# emitter.net
KiCad netlist of a schematic drawn in EAGLE
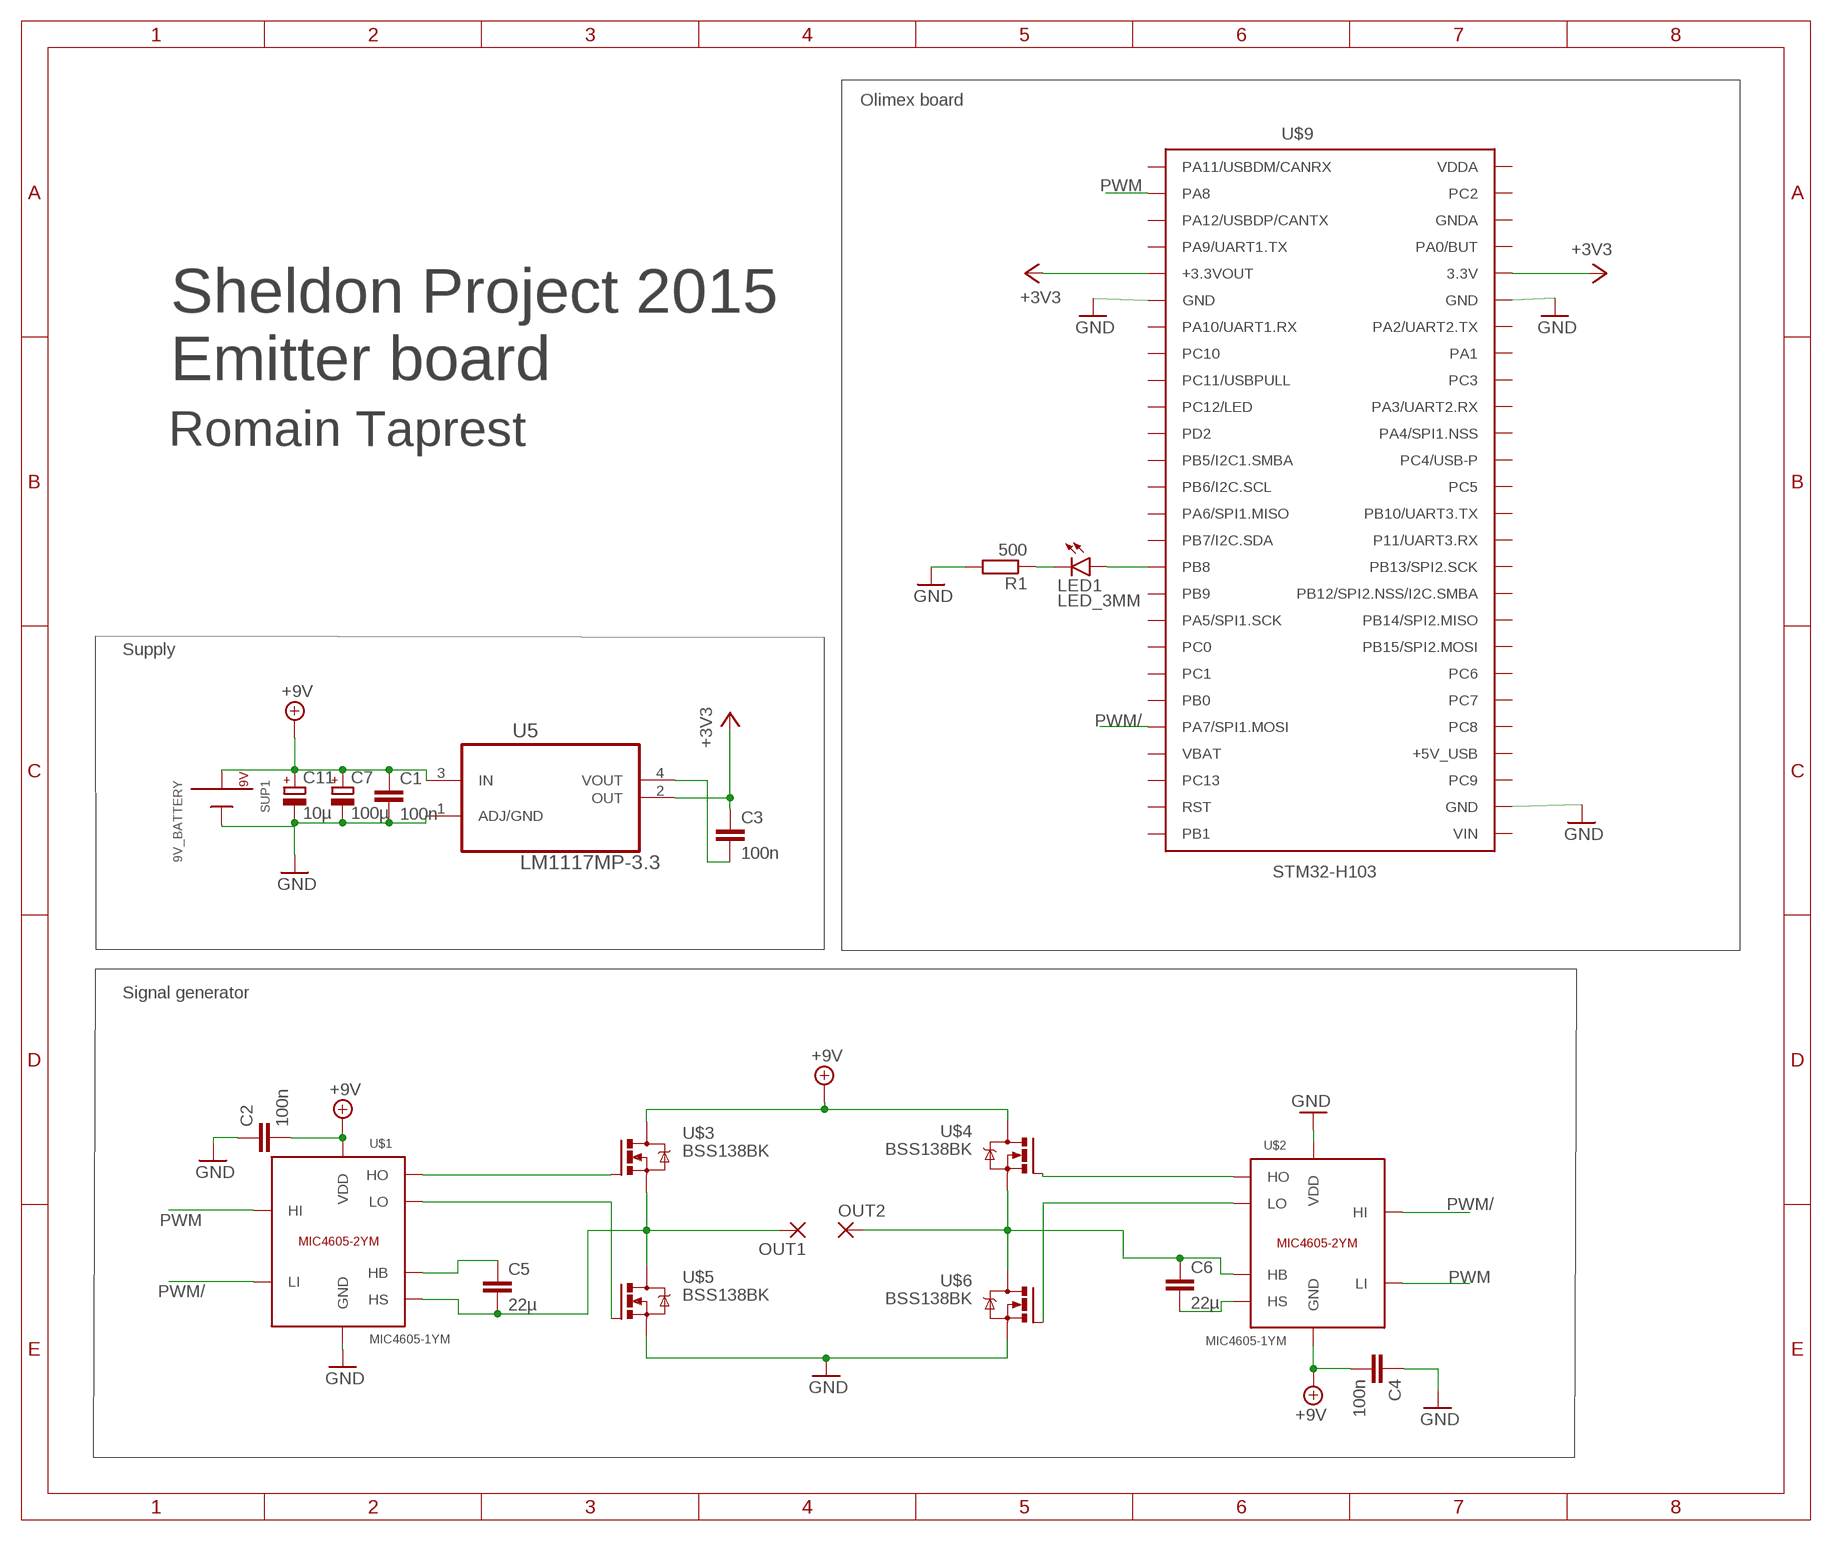
[diagram p0: schematic, sheet 1]

(export (version "E")
  (design (tool "Eeschema 10.0.6"))
  (components
    (comp (ref "C1")
      (value "100n")
      (footprint "eagle-import:C050-025X075")
      (libsource (lib "eagle-import") (part "C-EU050-025X075"))
    )
    (comp (ref "C2")
      (value "100n")
      (footprint "eagle-import:C050-025X075")
      (libsource (lib "eagle-import") (part "C-EU050-025X075"))
    )
    (comp (ref "C3")
      (value "100n")
      (footprint "eagle-import:C050-025X075")
      (libsource (lib "eagle-import") (part "C-EU050-025X075"))
    )
    (comp (ref "C4")
      (value "100n")
      (footprint "eagle-import:C050-025X075")
      (libsource (lib "eagle-import") (part "C-EU050-025X075"))
    )
    (comp (ref "C5")
      (value "22µ")
      (footprint "eagle-import:C050-025X075")
      (libsource (lib "eagle-import") (part "C-EU050-025X075"))
    )
    (comp (ref "C6")
      (value "22µ")
      (footprint "eagle-import:C050-025X075")
      (libsource (lib "eagle-import") (part "C-EU050-025X075"))
    )
    (comp (ref "C7")
      (value "100µ")
      (footprint "eagle-import:E2,5-6")
      (libsource (lib "eagle-import") (part "CPOL_DIAM5MM"))
    )
    (comp (ref "C11")
      (value "10µ")
      (footprint "eagle-import:E2,5-6")
      (libsource (lib "eagle-import") (part "CPOL_DIAM5MM"))
    )
    (comp (ref "LED1")
      (value "LED_3MM")
      (footprint "eagle-import:LED3MM")
      (libsource (lib "eagle-import") (part "LED_3MM"))
    )
    (comp (ref "OUT1")
      (value "2,54/1,0")
      (footprint "eagle-import:2,54_1,0")
      (libsource (lib "eagle-import") (part "2,54/1,0"))
    )
    (comp (ref "OUT2")
      (value "2,54/1,0")
      (footprint "eagle-import:2,54_1,0")
      (libsource (lib "eagle-import") (part "2,54/1,0"))
    )
    (comp (ref "R1")
      (value "500")
      (footprint "eagle-import:0207_10")
      (libsource (lib "eagle-import") (part "R-EU_0207/10"))
    )
    (comp (ref "SUP1")
      (value "9V_BATTERY")
      (footprint "eagle-import:9V_BATTERY")
      (libsource (lib "eagle-import") (part "9V_BATTERY"))
    )
    (comp (ref "U$1")
      (value "MIC4605-1YM")
      (footprint "eagle-import:SOIC08")
      (libsource (lib "eagle-import") (part "MIC4605-1YM"))
    )
    (comp (ref "U$2")
      (value "MIC4605-1YM")
      (footprint "eagle-import:SOIC08")
      (libsource (lib "eagle-import") (part "MIC4605-1YM"))
    )
    (comp (ref "U$3")
      (value "BSS138BK")
      (footprint "eagle-import:SOT23")
      (libsource (lib "eagle-import") (part "BSS138BK"))
    )
    (comp (ref "U$4")
      (value "BSS138BK")
      (footprint "eagle-import:SOT23")
      (libsource (lib "eagle-import") (part "BSS138BK"))
    )
    (comp (ref "U$5")
      (value "BSS138BK")
      (footprint "eagle-import:SOT23")
      (libsource (lib "eagle-import") (part "BSS138BK"))
    )
    (comp (ref "U$6")
      (value "BSS138BK")
      (footprint "eagle-import:SOT23")
      (libsource (lib "eagle-import") (part "BSS138BK"))
    )
    (comp (ref "U$9")
      (value "STM32-H103")
      (footprint "eagle-import:STM32-H103")
      (libsource (lib "eagle-import") (part "STM32-H103"))
    )
    (comp (ref "U5")
      (value "LM1117MP-3.3")
      (footprint "eagle-import:SOT230P696X180-4N")
      (libsource (lib "eagle-import") (part "LM1117MP-3.3"))
    )
  )
  (nets
    (net (code "1") (name "+3V3") (class "Default")
      (node (ref "C3") (pin "1") (pinfunction "1_1") (pintype "passive"))
      (node (ref "U$9") (pin "+3.3VOUT") (pinfunction "+3.3VOUT_+3.3VOUT") (pintype "bidirectional"))
      (node (ref "U$9") (pin "3.3V") (pinfunction "3.3V_3.3V") (pintype "bidirectional"))
      (node (ref "U5") (pin "2") (pinfunction "OUT_2") (pintype "output"))
    )
    (net (code "2") (name "+9V") (class "Default")
      (node (ref "C1") (pin "1") (pinfunction "1_1") (pintype "passive"))
      (node (ref "C11") (pin "+") (pinfunction "P$1_+") (pintype "passive"))
      (node (ref "C2") (pin "2") (pinfunction "2_2") (pintype "passive"))
      (node (ref "C4") (pin "2") (pinfunction "2_2") (pintype "passive"))
      (node (ref "C7") (pin "+") (pinfunction "P$1_+") (pintype "passive"))
      (node (ref "SUP1") (pin "P$1") (pinfunction "9V_P$1") (pintype "power_in"))
      (node (ref "U$1") (pin "1") (pinfunction "VDD_1") (pintype "power_in"))
      (node (ref "U$2") (pin "7") (pinfunction "GND_7") (pintype "power_in"))
      (node (ref "U$3") (pin "3") (pinfunction "D_3") (pintype "passive"))
      (node (ref "U$4") (pin "3") (pinfunction "D_3") (pintype "passive"))
      (node (ref "U5") (pin "3") (pinfunction "IN_3") (pintype "input"))
    )
    (net (code "3") (name "/PWM") (class "Default")
      (node (ref "U$1") (pin "5") (pinfunction "HI_5") (pintype "input"))
      (node (ref "U$2") (pin "6") (pinfunction "LI_6") (pintype "input"))
      (node (ref "U$9") (pin "PA8") (pinfunction "PA8_PA8") (pintype "bidirectional"))
    )
    (net (code "4") (name "/PWM{slash}") (class "Default")
      (node (ref "U$1") (pin "6") (pinfunction "LI_6") (pintype "input"))
      (node (ref "U$2") (pin "5") (pinfunction "HI_5") (pintype "input"))
      (node (ref "U$9") (pin "PA7/SPI1.MOSI") (pinfunction "PA7/SPI1.MOSI_PA7/SPI1.MOSI") (pintype "bidirectional"))
    )
    (net (code "5") (name "GND") (class "Default")
      (node (ref "C1") (pin "2") (pinfunction "2_2") (pintype "passive"))
      (node (ref "C11") (pin "-") (pinfunction "P$2_-") (pintype "passive"))
      (node (ref "C2") (pin "1") (pinfunction "1_1") (pintype "passive"))
      (node (ref "C4") (pin "1") (pinfunction "1_1") (pintype "passive"))
      (node (ref "C7") (pin "-") (pinfunction "P$2_-") (pintype "passive"))
      (node (ref "R1") (pin "2") (pinfunction "2_2") (pintype "passive"))
      (node (ref "SUP1") (pin "P$2") (pinfunction "GND_P$2") (pintype "power_in"))
      (node (ref "U$1") (pin "7") (pinfunction "GND_7") (pintype "power_in"))
      (node (ref "U$2") (pin "1") (pinfunction "VDD_1") (pintype "power_in"))
      (node (ref "U$5") (pin "2") (pinfunction "S_2") (pintype "passive"))
      (node (ref "U$6") (pin "2") (pinfunction "S_2") (pintype "passive"))
      (node (ref "U$9") (pin "GND@1") (pinfunction "GND_GND@1") (pintype "bidirectional"))
      (node (ref "U$9") (pin "GND@2") (pinfunction "GND_GND@2") (pintype "bidirectional"))
      (node (ref "U$9") (pin "GND@3") (pinfunction "GND_GND@3") (pintype "bidirectional"))
      (node (ref "U5") (pin "1") (pinfunction "ADJ/GND_1") (pintype "passive"))
    )
    (net (code "6") (name "Net-(LED1-C)") (class "Default")
      (node (ref "LED1") (pin "K") (pinfunction "C_K") (pintype "passive"))
      (node (ref "R1") (pin "1") (pinfunction "1_1") (pintype "passive"))
    )
    (net (code "7") (name "Net-(LED1-PadA)") (class "Default")
      (node (ref "LED1") (pin "A") (pinfunction "A_A") (pintype "passive"))
      (node (ref "U$9") (pin "PB8") (pinfunction "PB8_PB8") (pintype "bidirectional"))
    )
    (net (code "8") (name "Net-(OUT1-P)") (class "Default")
      (node (ref "C5") (pin "2") (pinfunction "2_2") (pintype "passive"))
      (node (ref "OUT1") (pin "1") (pinfunction "P_1") (pintype "passive"))
      (node (ref "U$1") (pin "4") (pinfunction "HS_4") (pintype "output"))
      (node (ref "U$3") (pin "2") (pinfunction "S_2") (pintype "passive"))
      (node (ref "U$5") (pin "3") (pinfunction "D_3") (pintype "passive"))
    )
    (net (code "9") (name "Net-(OUT2-P)") (class "Default")
      (node (ref "C6") (pin "1") (pinfunction "1_1") (pintype "passive"))
      (node (ref "OUT2") (pin "1") (pinfunction "P_1") (pintype "passive"))
      (node (ref "U$2") (pin "2") (pinfunction "HB_2") (pintype "output"))
      (node (ref "U$4") (pin "2") (pinfunction "S_2") (pintype "passive"))
      (node (ref "U$6") (pin "3") (pinfunction "D_3") (pintype "passive"))
    )
    (net (code "10") (name "Net-(U$1-HB)") (class "Default")
      (node (ref "C5") (pin "1") (pinfunction "1_1") (pintype "passive"))
      (node (ref "U$1") (pin "2") (pinfunction "HB_2") (pintype "output"))
    )
    (net (code "11") (name "Net-(U$1-HO)") (class "Default")
      (node (ref "U$1") (pin "3") (pinfunction "HO_3") (pintype "output"))
      (node (ref "U$3") (pin "1") (pinfunction "G_1") (pintype "passive"))
    )
    (net (code "12") (name "Net-(U$1-LO)") (class "Default")
      (node (ref "U$1") (pin "8") (pinfunction "LO_8") (pintype "output"))
      (node (ref "U$5") (pin "1") (pinfunction "G_1") (pintype "passive"))
    )
    (net (code "13") (name "Net-(U$2-HO)") (class "Default")
      (node (ref "U$2") (pin "3") (pinfunction "HO_3") (pintype "output"))
      (node (ref "U$4") (pin "1") (pinfunction "G_1") (pintype "passive"))
    )
    (net (code "14") (name "Net-(U$2-HS)") (class "Default")
      (node (ref "C6") (pin "2") (pinfunction "2_2") (pintype "passive"))
      (node (ref "U$2") (pin "4") (pinfunction "HS_4") (pintype "output"))
    )
    (net (code "15") (name "Net-(U$2-LO)") (class "Default")
      (node (ref "U$2") (pin "8") (pinfunction "LO_8") (pintype "output"))
      (node (ref "U$6") (pin "1") (pinfunction "G_1") (pintype "passive"))
    )
    (net (code "16") (name "Net-(U5-VOUT)") (class "Default")
      (node (ref "C3") (pin "2") (pinfunction "2_2") (pintype "passive"))
      (node (ref "U5") (pin "4") (pinfunction "VOUT_4") (pintype "output"))
    )
    (net (code "17") (name "unconnected-(U$9-Pad+5V_USB)") (class "Default")
      (node (ref "U$9") (pin "+5V_USB") (pinfunction "+5V_USB_+5V_USB") (pintype "bidirectional"))
    )
    (net (code "18") (name "unconnected-(U$9-PadGNDA)") (class "Default")
      (node (ref "U$9") (pin "GNDA") (pinfunction "GNDA_GNDA") (pintype "bidirectional"))
    )
    (net (code "19") (name "unconnected-(U$9-PadP11{slash}UART3.RX)") (class "Default")
      (node (ref "U$9") (pin "P11/UART3.RX") (pinfunction "P11/UART3.RX_P11/UART3.RX") (pintype "bidirectional"))
    )
    (net (code "20") (name "unconnected-(U$9-PadPA0{slash}BUT)") (class "Default")
      (node (ref "U$9") (pin "PA0/BUT") (pinfunction "PA0/BUT_PA0/BUT") (pintype "bidirectional"))
    )
    (net (code "21") (name "unconnected-(U$9-PadPA1)") (class "Default")
      (node (ref "U$9") (pin "PA1") (pinfunction "PA1_PA1") (pintype "bidirectional"))
    )
    (net (code "22") (name "unconnected-(U$9-PadPA2{slash}UART2.TX)") (class "Default")
      (node (ref "U$9") (pin "PA2/UART2.TX") (pinfunction "PA2/UART2.TX_PA2/UART2.TX") (pintype "bidirectional"))
    )
    (net (code "23") (name "unconnected-(U$9-PadPA3{slash}UART2.RX)") (class "Default")
      (node (ref "U$9") (pin "PA3/UART2.RX") (pinfunction "PA3/UART2.RX_PA3/UART2.RX") (pintype "bidirectional"))
    )
    (net (code "24") (name "unconnected-(U$9-PadPA4{slash}SPI1.NSS)") (class "Default")
      (node (ref "U$9") (pin "PA4/SPI1.NSS") (pinfunction "PA4/SPI1.NSS_PA4/SPI1.NSS") (pintype "bidirectional"))
    )
    (net (code "25") (name "unconnected-(U$9-PadPA5{slash}SPI1.SCK)") (class "Default")
      (node (ref "U$9") (pin "PA5/SPI1.SCK") (pinfunction "PA5/SPI1.SCK_PA5/SPI1.SCK") (pintype "bidirectional"))
    )
    (net (code "26") (name "unconnected-(U$9-PadPA6{slash}SPI1.MISO)") (class "Default")
      (node (ref "U$9") (pin "PA6/SPI1.MISO") (pinfunction "PA6/SPI1.MISO_PA6/SPI1.MISO") (pintype "bidirectional"))
    )
    (net (code "27") (name "unconnected-(U$9-PadPA9{slash}UART1.TX)") (class "Default")
      (node (ref "U$9") (pin "PA9/UART1.TX") (pinfunction "PA9/UART1.TX_PA9/UART1.TX") (pintype "bidirectional"))
    )
    (net (code "28") (name "unconnected-(U$9-PadPA10{slash}UART1.RX)") (class "Default")
      (node (ref "U$9") (pin "PA10/UART1.RX") (pinfunction "PA10/UART1.RX_PA10/UART1.RX") (pintype "bidirectional"))
    )
    (net (code "29") (name "unconnected-(U$9-PadPA11{slash}USBDM{slash}CANRX)") (class "Default")
      (node (ref "U$9") (pin "PA11/USBDM/CANRX") (pinfunction "PA11/USBDM/CANRX_PA11/USBDM/CANRX") (pintype "bidirectional"))
    )
    (net (code "30") (name "unconnected-(U$9-PadPA12{slash}USBDP{slash}CANTX)") (class "Default")
      (node (ref "U$9") (pin "PA12/USBDP/CANTX") (pinfunction "PA12/USBDP/CANTX_PA12/USBDP/CANTX") (pintype "bidirectional"))
    )
    (net (code "31") (name "unconnected-(U$9-PadPB0)") (class "Default")
      (node (ref "U$9") (pin "PB0") (pinfunction "PB0_PB0") (pintype "bidirectional"))
    )
    (net (code "32") (name "unconnected-(U$9-PadPB1)") (class "Default")
      (node (ref "U$9") (pin "PB1") (pinfunction "PB1_PB1") (pintype "bidirectional"))
    )
    (net (code "33") (name "unconnected-(U$9-PadPB5{slash}I2C1.SMBA)") (class "Default")
      (node (ref "U$9") (pin "PB5/I2C1.SMBA") (pinfunction "PB5/I2C1.SMBA_PB5/I2C1.SMBA") (pintype "bidirectional"))
    )
    (net (code "34") (name "unconnected-(U$9-PadPB6{slash}I2C.SCL)") (class "Default")
      (node (ref "U$9") (pin "PB6/I2C.SCL") (pinfunction "PB6/I2C.SCL_PB6/I2C.SCL") (pintype "bidirectional"))
    )
    (net (code "35") (name "unconnected-(U$9-PadPB7{slash}I2C.SDA)") (class "Default")
      (node (ref "U$9") (pin "PB7/I2C.SDA") (pinfunction "PB7/I2C.SDA_PB7/I2C.SDA") (pintype "bidirectional"))
    )
    (net (code "36") (name "unconnected-(U$9-PadPB9)") (class "Default")
      (node (ref "U$9") (pin "PB9") (pinfunction "PB9_PB9") (pintype "bidirectional"))
    )
    (net (code "37") (name "unconnected-(U$9-PadPB10{slash}UART3.TX)") (class "Default")
      (node (ref "U$9") (pin "PB10/UART3.TX") (pinfunction "PB10/UART3.TX_PB10/UART3.TX") (pintype "bidirectional"))
    )
    (net (code "38") (name "unconnected-(U$9-PadPB12{slash}SPI2.NSS{slash}I2C.SMBA)") (class "Default")
      (node (ref "U$9") (pin "PB12/SPI2.NSS/I2C.SMBA") (pinfunction "PB12/SPI2.NSS/I2C.SMBA_PB12/SPI2.NSS/I2C.SMBA") (pintype "bidirectional"))
    )
    (net (code "39") (name "unconnected-(U$9-PadPB13{slash}SPI2.SCK)") (class "Default")
      (node (ref "U$9") (pin "PB13/SPI2.SCK") (pinfunction "PB13/SPI2.SCK_PB13/SPI2.SCK") (pintype "bidirectional"))
    )
    (net (code "40") (name "unconnected-(U$9-PadPB14{slash}SPI2.MISO)") (class "Default")
      (node (ref "U$9") (pin "PB14/SPI2.MISO") (pinfunction "PB14/SPI2.MISO_PB14/SPI2.MISO") (pintype "bidirectional"))
    )
    (net (code "41") (name "unconnected-(U$9-PadPB15{slash}SPI2.MOSI)") (class "Default")
      (node (ref "U$9") (pin "PB15/SPI2.MOSI") (pinfunction "PB15/SPI2.MOSI_PB15/SPI2.MOSI") (pintype "bidirectional"))
    )
    (net (code "42") (name "unconnected-(U$9-PadPC0)") (class "Default")
      (node (ref "U$9") (pin "PC0") (pinfunction "PC0_PC0") (pintype "bidirectional"))
    )
    (net (code "43") (name "unconnected-(U$9-PadPC1)") (class "Default")
      (node (ref "U$9") (pin "PC1") (pinfunction "PC1_PC1") (pintype "bidirectional"))
    )
    (net (code "44") (name "unconnected-(U$9-PadPC2)") (class "Default")
      (node (ref "U$9") (pin "PC2") (pinfunction "PC2_PC2") (pintype "bidirectional"))
    )
    (net (code "45") (name "unconnected-(U$9-PadPC3)") (class "Default")
      (node (ref "U$9") (pin "PC3") (pinfunction "PC3_PC3") (pintype "bidirectional"))
    )
    (net (code "46") (name "unconnected-(U$9-PadPC4{slash}USB-P)") (class "Default")
      (node (ref "U$9") (pin "PC4/USB-P") (pinfunction "PC4/USB-P_PC4/USB-P") (pintype "bidirectional"))
    )
    (net (code "47") (name "unconnected-(U$9-PadPC5)") (class "Default")
      (node (ref "U$9") (pin "PC5") (pinfunction "PC5_PC5") (pintype "bidirectional"))
    )
    (net (code "48") (name "unconnected-(U$9-PadPC6)") (class "Default")
      (node (ref "U$9") (pin "PC6") (pinfunction "PC6_PC6") (pintype "bidirectional"))
    )
    (net (code "49") (name "unconnected-(U$9-PadPC7)") (class "Default")
      (node (ref "U$9") (pin "PC7") (pinfunction "PC7_PC7") (pintype "bidirectional"))
    )
    (net (code "50") (name "unconnected-(U$9-PadPC8)") (class "Default")
      (node (ref "U$9") (pin "PC8") (pinfunction "PC8_PC8") (pintype "bidirectional"))
    )
    (net (code "51") (name "unconnected-(U$9-PadPC9)") (class "Default")
      (node (ref "U$9") (pin "PC9") (pinfunction "PC9_PC9") (pintype "bidirectional"))
    )
    (net (code "52") (name "unconnected-(U$9-PadPC10)") (class "Default")
      (node (ref "U$9") (pin "PC10") (pinfunction "PC10_PC10") (pintype "bidirectional"))
    )
    (net (code "53") (name "unconnected-(U$9-PadPC11{slash}USBPULL)") (class "Default")
      (node (ref "U$9") (pin "PC11/USBPULL") (pinfunction "PC11/USBPULL_PC11/USBPULL") (pintype "bidirectional"))
    )
    (net (code "54") (name "unconnected-(U$9-PadPC12{slash}LED)") (class "Default")
      (node (ref "U$9") (pin "PC12/LED") (pinfunction "PC12/LED_PC12/LED") (pintype "bidirectional"))
    )
    (net (code "55") (name "unconnected-(U$9-PadPC13)") (class "Default")
      (node (ref "U$9") (pin "PC13") (pinfunction "PC13_PC13") (pintype "bidirectional"))
    )
    (net (code "56") (name "unconnected-(U$9-PadPD2)") (class "Default")
      (node (ref "U$9") (pin "PD2") (pinfunction "PD2_PD2") (pintype "bidirectional"))
    )
    (net (code "57") (name "unconnected-(U$9-PadRST)") (class "Default")
      (node (ref "U$9") (pin "RST") (pinfunction "RST_RST") (pintype "bidirectional"))
    )
    (net (code "58") (name "unconnected-(U$9-PadVBAT)") (class "Default")
      (node (ref "U$9") (pin "VBAT") (pinfunction "VBAT_VBAT") (pintype "bidirectional"))
    )
    (net (code "59") (name "unconnected-(U$9-PadVDDA)") (class "Default")
      (node (ref "U$9") (pin "VDDA") (pinfunction "VDDA_VDDA") (pintype "bidirectional"))
    )
    (net (code "60") (name "unconnected-(U$9-PadVIN)") (class "Default")
      (node (ref "U$9") (pin "VIN") (pinfunction "VIN_VIN") (pintype "bidirectional"))
    )
  )
)
